# LM_HTR_001.net
KiCad netlist of a schematic drawn in Altium Designer
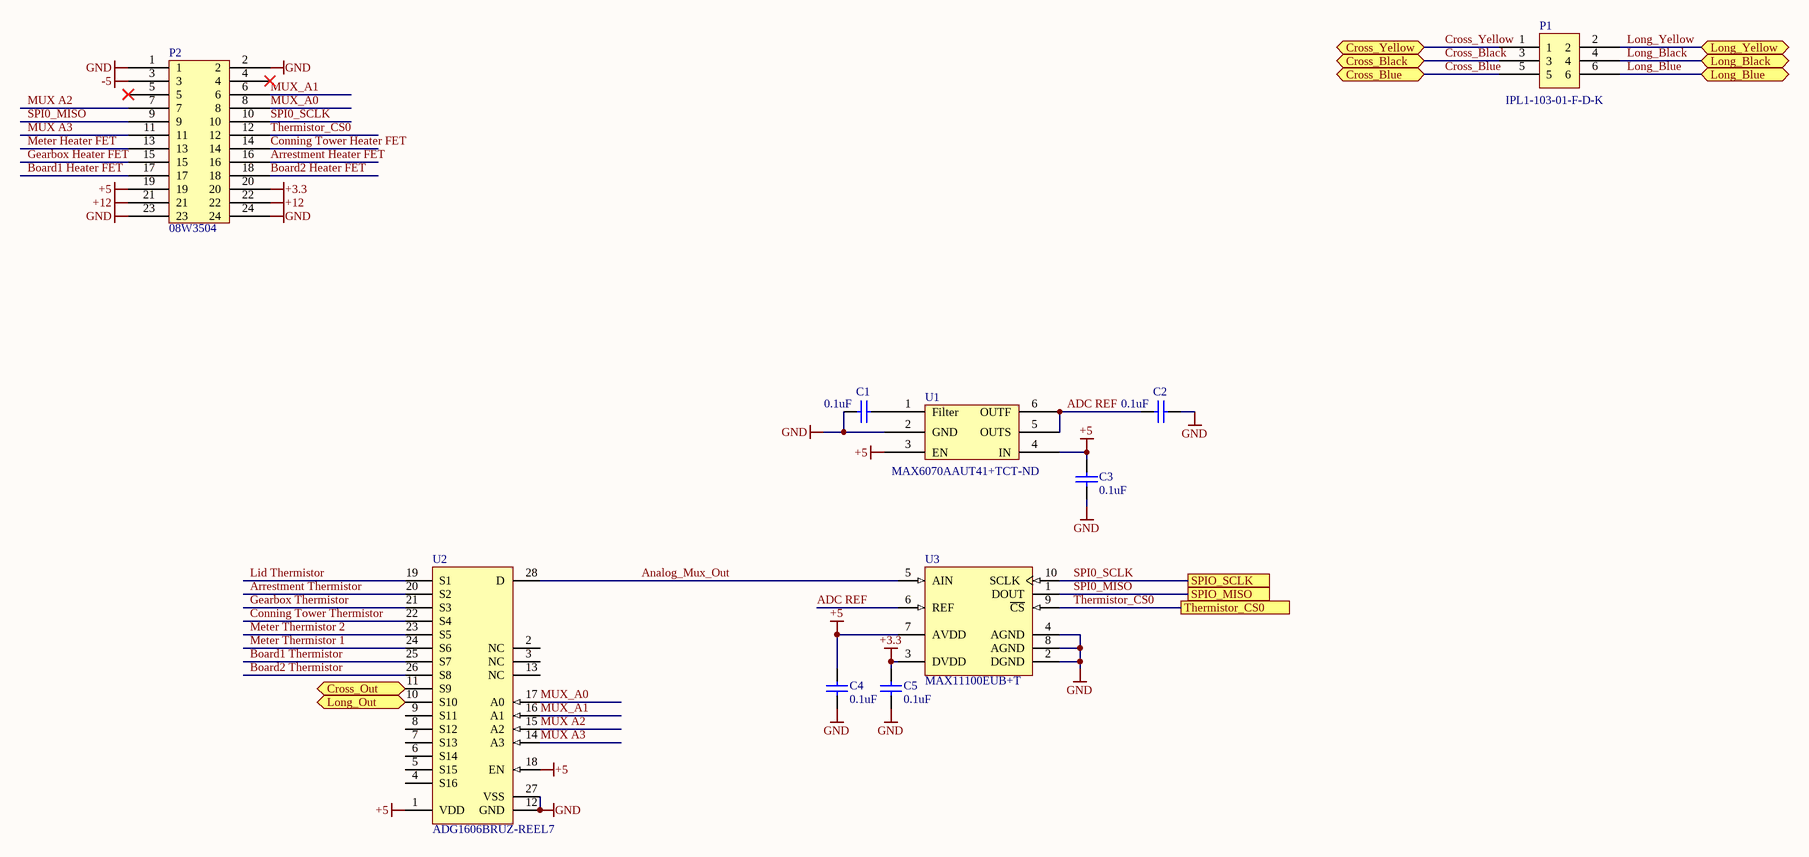
[diagram p0: LM_HTR_001.SchDoc]

(export (version "E")
  (design (tool "Eeschema 10.0.6"))
  (components
    (comp (ref "C1")
      (value "0.1uF")
      (footprint "CAPC0402(1005)60_L")
      (description "CAP CER 0.1UF 10V X7R 0402")
      (fields
        (field (name "MANUFACTURER") "Murata Electronics North America")
        (field (name "MANUFACTURER PART NUMBER") "GRM155R71A104KA01D")
      )
      (libsource (lib "Altium Content Vault") (part "CMP-1034-00252-1"))
    )
    (comp (ref "C2")
      (value "0.1uF")
      (footprint "CAPC0402(1005)60_L")
      (description "CAP CER 0.1UF 10V X7R 0402")
      (fields
        (field (name "MANUFACTURER") "Murata Electronics North America")
        (field (name "MANUFACTURER PART NUMBER") "GRM155R71A104KA01D")
      )
      (libsource (lib "Altium Content Vault") (part "CMP-1034-00252-1"))
    )
    (comp (ref "C3")
      (value "0.1uF")
      (footprint "CAPC0402(1005)60_L")
      (description "CAP CER 0.1UF 10V X7R 0402")
      (fields
        (field (name "MANUFACTURER") "Murata Electronics North America")
        (field (name "MANUFACTURER PART NUMBER") "GRM155R71A104KA01D")
      )
      (libsource (lib "Altium Content Vault") (part "CMP-1034-00252-1"))
    )
    (comp (ref "C4")
      (value "0.1uF")
      (footprint "CAPC0402(1005)60_L")
      (description "CAP CER 0.1UF 10V X7R 0402")
      (fields
        (field (name "MANUFACTURER") "Murata Electronics North America")
        (field (name "MANUFACTURER PART NUMBER") "GRM155R71A104KA01D")
      )
      (libsource (lib "Altium Content Vault") (part "CMP-1034-00252-1"))
    )
    (comp (ref "C5")
      (value "0.1uF")
      (footprint "CAPC0402(1005)60_L")
      (description "CAP CER 0.1UF 10V X7R 0402")
      (fields
        (field (name "MANUFACTURER") "Murata Electronics North America")
        (field (name "MANUFACTURER PART NUMBER") "GRM155R71A104KA01D")
      )
      (libsource (lib "Altium Content Vault") (part "CMP-1034-00252-1"))
    )
    (comp (ref "P1")
      (value "IPL1-103-01-F-D")
      (footprint "IPL1-103-01-F-D")
      (fields
        (field (name "MANUFACTURER") "SAMTEC")
        (field (name "MANUFACTURER PART NUMBER") "IPL1-103-01-F-D-K")
        (field (name "COMPONENTLINK1URL") "https://webassistants.partcommunity.com/23d-libs/samtec/search/resolve.html?EMAIL=mysamtec@samtec.com&PN=HTSW-114-05-F-D")
        (field (name "COMPONENTLINK1DESCRIPTION") "https://webassistants.partcommunity.com/23d-libs/samtec/search/resolve.html?EMAIL=mysamtec@samtec.com&PN=HTSW-114-05-F-D")
      )
      (libsource (lib "ZLS_Schematic_lib") (part "IPL1-103-01-F-D"))
    )
    (comp (ref "P2")
      (value "IPL1-112-01-F-S-K")
      (footprint "IPL1-112-01-F-S-K")
      (description "IPL1-112-01-F-D-K")
      (fields (field (name "SUPPLIER PART NUMBER 1") "08W3504"))
      (libsource (lib "ZLS_Schematic_lib") (part "IPL1-112-01-F-S-K"))
    )
    (comp (ref "U1")
      (value "MAX6070AAUT41+T")
      (footprint "SOT95P280X445-6N")
      (description "IC VREF SERIES 4.096V SOT23")
      (fields
        (field (name "SUPPLIER PART NUMBER 1") "MAX6070AAUT41+TCT-ND")
        (field (name "MANUFACTURER") "Maxim Integrated")
        (field (name "TOLERANCE") "±0.04%")
      )
      (libsource (lib "ZLS_Schematic_lib") (part "MAX6070AAUT41+T"))
    )
    (comp (ref "U2")
      (value "ADG1606BRUZ-REEL7")
      (footprint "ADI-RU-28_M")
      (description "4.5 Ohm Ron, 16-Channel, +/-5 V,+12 V,+5 V and +3.3 V Multiplexer, 28-pin SOP (RU-28), Reel")
      (fields (field (name "MANUFACTURER") "Analog Devices"))
      (libsource (lib "Altium Content Vault") (part "ADI-ADG1606-RU-28"))
    )
    (comp (ref "U3")
      (value "MAX11100EUB+T")
      (footprint "U10+2_L")
      (description "16-Bit, +5V, 200ksps ADC with 10uA Shutdown, 10-Pin uMAX, -40°C to +85°C, Pb-Free, Tape and Reel")
      (libsource (lib "Altium Content Vault") (part "CON-ADC-MAX11100-IL10"))
    )
  )
  (nets
    (net (code "1") (name "+3.3") (class "Default")
      (node (ref "C5") (pin "1") (pinfunction "1_1") (pintype "passive"))
      (node (ref "P2") (pin "20") (pinfunction "20_20") (pintype "passive"))
      (node (ref "U3") (pin "3") (pinfunction "DVDD_3") (pintype "power_in"))
    )
    (net (code "2") (name "+5") (class "Default")
      (node (ref "C3") (pin "1") (pinfunction "1_1") (pintype "passive"))
      (node (ref "C4") (pin "1") (pinfunction "1_1") (pintype "passive"))
      (node (ref "P2") (pin "19") (pinfunction "19_19") (pintype "passive"))
      (node (ref "U1") (pin "3") (pinfunction "EN_3") (pintype "passive"))
      (node (ref "U1") (pin "4") (pinfunction "IN_4") (pintype "passive"))
      (node (ref "U2") (pin "1") (pinfunction "VDD_1") (pintype "power_in"))
      (node (ref "U2") (pin "18") (pinfunction "EN_18") (pintype "input"))
      (node (ref "U3") (pin "7") (pinfunction "AVDD_7") (pintype "power_in"))
    )
    (net (code "3") (name "+12") (class "Default")
      (node (ref "P2") (pin "21") (pinfunction "21_21") (pintype "passive"))
      (node (ref "P2") (pin "22") (pinfunction "22_22") (pintype "passive"))
    )
    (net (code "4") (name "-5") (class "Default")
      (node (ref "P2") (pin "3") (pinfunction "3_3") (pintype "passive"))
    )
    (net (code "5") (name "/ADC REF") (class "Default")
      (node (ref "C2") (pin "2") (pinfunction "2_2") (pintype "passive"))
      (node (ref "U1") (pin "5") (pinfunction "OUTS_5") (pintype "passive"))
      (node (ref "U1") (pin "6") (pinfunction "OUTF_6") (pintype "passive"))
      (node (ref "U3") (pin "6") (pinfunction "REF_6") (pintype "input"))
    )
    (net (code "6") (name "/Analog_Mux_Out") (class "Default")
      (node (ref "U2") (pin "28") (pinfunction "D_28") (pintype "passive"))
      (node (ref "U3") (pin "5") (pinfunction "AIN_5") (pintype "input"))
    )
    (net (code "7") (name "/Arrestment Heater FET") (class "Default")
      (node (ref "P2") (pin "16") (pinfunction "16_16") (pintype "passive"))
    )
    (net (code "8") (name "/Arrestment Thermistor") (class "Default")
      (node (ref "U2") (pin "20") (pinfunction "S2_20") (pintype "passive"))
    )
    (net (code "9") (name "/Board1 Heater FET") (class "Default")
      (node (ref "P2") (pin "17") (pinfunction "17_17") (pintype "passive"))
    )
    (net (code "10") (name "/Board1 Thermistor") (class "Default")
      (node (ref "U2") (pin "25") (pinfunction "S7_25") (pintype "passive"))
    )
    (net (code "11") (name "/Board2 Heater FET") (class "Default")
      (node (ref "P2") (pin "18") (pinfunction "18_18") (pintype "passive"))
    )
    (net (code "12") (name "/Board2 Thermistor") (class "Default")
      (node (ref "U2") (pin "26") (pinfunction "S8_26") (pintype "passive"))
    )
    (net (code "13") (name "/Conning Tower Heater FET") (class "Default")
      (node (ref "P2") (pin "14") (pinfunction "14_14") (pintype "passive"))
    )
    (net (code "14") (name "/Conning Tower Thermistor") (class "Default")
      (node (ref "U2") (pin "22") (pinfunction "S4_22") (pintype "passive"))
    )
    (net (code "15") (name "/Cross_Black") (class "Default")
      (node (ref "P1") (pin "3") (pinfunction "3_3") (pintype "passive"))
    )
    (net (code "16") (name "/Cross_Blue") (class "Default")
      (node (ref "P1") (pin "5") (pinfunction "5_5") (pintype "passive"))
    )
    (net (code "17") (name "/Cross_Out") (class "Default")
      (node (ref "U2") (pin "11") (pinfunction "S9_11") (pintype "passive"))
    )
    (net (code "18") (name "/Cross_Yellow") (class "Default")
      (node (ref "P1") (pin "1") (pinfunction "1_1") (pintype "passive"))
    )
    (net (code "19") (name "/Gearbox Heater FET") (class "Default")
      (node (ref "P2") (pin "15") (pinfunction "15_15") (pintype "passive"))
    )
    (net (code "20") (name "/Gearbox Thermistor") (class "Default")
      (node (ref "U2") (pin "21") (pinfunction "S3_21") (pintype "passive"))
    )
    (net (code "21") (name "/Lid Thermistor") (class "Default")
      (node (ref "U2") (pin "19") (pinfunction "S1_19") (pintype "passive"))
    )
    (net (code "22") (name "/Long_Black") (class "Default")
      (node (ref "P1") (pin "4") (pinfunction "4_4") (pintype "passive"))
    )
    (net (code "23") (name "/Long_Blue") (class "Default")
      (node (ref "P1") (pin "6") (pinfunction "6_6") (pintype "passive"))
    )
    (net (code "24") (name "/Long_Out") (class "Default")
      (node (ref "U2") (pin "10") (pinfunction "S10_10") (pintype "passive"))
    )
    (net (code "25") (name "/Long_Yellow") (class "Default")
      (node (ref "P1") (pin "2") (pinfunction "2_2") (pintype "passive"))
    )
    (net (code "26") (name "/MUX A2") (class "Default")
      (node (ref "P2") (pin "7") (pinfunction "7_7") (pintype "passive"))
      (node (ref "U2") (pin "15") (pinfunction "A2_15") (pintype "input"))
    )
    (net (code "27") (name "/MUX A3") (class "Default")
      (node (ref "P2") (pin "11") (pinfunction "11_11") (pintype "passive"))
      (node (ref "U2") (pin "14") (pinfunction "A3_14") (pintype "input"))
    )
    (net (code "28") (name "/MUX_A0") (class "Default")
      (node (ref "P2") (pin "8") (pinfunction "8_8") (pintype "passive"))
      (node (ref "U2") (pin "17") (pinfunction "A0_17") (pintype "input"))
    )
    (net (code "29") (name "/MUX_A1") (class "Default")
      (node (ref "P2") (pin "6") (pinfunction "6_6") (pintype "passive"))
      (node (ref "U2") (pin "16") (pinfunction "A1_16") (pintype "input"))
    )
    (net (code "30") (name "/Meter Heater FET") (class "Default")
      (node (ref "P2") (pin "13") (pinfunction "13_13") (pintype "passive"))
    )
    (net (code "31") (name "/Meter Thermistor 1") (class "Default")
      (node (ref "U2") (pin "24") (pinfunction "S6_24") (pintype "passive"))
    )
    (net (code "32") (name "/Meter Thermistor 2") (class "Default")
      (node (ref "U2") (pin "23") (pinfunction "S5_23") (pintype "passive"))
    )
    (net (code "33") (name "/SPI0_MISO") (class "Default")
      (node (ref "P2") (pin "9") (pinfunction "9_9") (pintype "passive"))
      (node (ref "U3") (pin "1") (pinfunction "DOUT_1") (pintype "tri_state"))
    )
    (net (code "34") (name "/SPI0_SCLK") (class "Default")
      (node (ref "P2") (pin "10") (pinfunction "10_10") (pintype "passive"))
      (node (ref "U3") (pin "10") (pinfunction "SCLK_10") (pintype "input"))
    )
    (net (code "35") (name "/Thermistor_CS0") (class "Default")
      (node (ref "P2") (pin "12") (pinfunction "12_12") (pintype "passive"))
      (node (ref "U3") (pin "9") (pinfunction "~{CS}_9") (pintype "input"))
    )
    (net (code "36") (name "GND") (class "Default")
      (node (ref "C1") (pin "2") (pinfunction "2_2") (pintype "passive"))
      (node (ref "C2") (pin "1") (pinfunction "1_1") (pintype "passive"))
      (node (ref "C3") (pin "2") (pinfunction "2_2") (pintype "passive"))
      (node (ref "C4") (pin "2") (pinfunction "2_2") (pintype "passive"))
      (node (ref "C5") (pin "2") (pinfunction "2_2") (pintype "passive"))
      (node (ref "P2") (pin "1") (pinfunction "1_1") (pintype "passive"))
      (node (ref "P2") (pin "2") (pinfunction "2_2") (pintype "passive"))
      (node (ref "P2") (pin "23") (pinfunction "23_23") (pintype "passive"))
      (node (ref "P2") (pin "24") (pinfunction "24_24") (pintype "passive"))
      (node (ref "U1") (pin "2") (pinfunction "GND_2") (pintype "passive"))
      (node (ref "U2") (pin "12") (pinfunction "GND_12") (pintype "power_in"))
      (node (ref "U2") (pin "27") (pinfunction "VSS_27") (pintype "power_in"))
      (node (ref "U3") (pin "2") (pinfunction "DGND_2") (pintype "power_in"))
      (node (ref "U3") (pin "4") (pinfunction "AGND_4") (pintype "power_in"))
      (node (ref "U3") (pin "8") (pinfunction "AGND_8") (pintype "power_in"))
    )
    (net (code "37") (name "Net-(U1-Filter)") (class "Default")
      (node (ref "C1") (pin "1") (pinfunction "1_1") (pintype "passive"))
      (node (ref "U1") (pin "1") (pinfunction "Filter_1") (pintype "passive"))
    )
    (net (code "38") (name "unconnected-(P2-Pad4)") (class "Default")
      (node (ref "P2") (pin "4") (pinfunction "4_4") (pintype "passive+no_connect"))
    )
    (net (code "39") (name "unconnected-(P2-Pad5)") (class "Default")
      (node (ref "P2") (pin "5") (pinfunction "5_5") (pintype "passive+no_connect"))
    )
    (net (code "40") (name "unconnected-(U2-NC-Pad2)") (class "Default")
      (node (ref "U2") (pin "2") (pinfunction "NC_2") (pintype "passive"))
    )
    (net (code "41") (name "unconnected-(U2-NC-Pad3)") (class "Default")
      (node (ref "U2") (pin "3") (pinfunction "NC_3") (pintype "passive"))
    )
    (net (code "42") (name "unconnected-(U2-NC-Pad13)") (class "Default")
      (node (ref "U2") (pin "13") (pinfunction "NC_13") (pintype "passive"))
    )
    (net (code "43") (name "unconnected-(U2-S11-Pad9)") (class "Default")
      (node (ref "U2") (pin "9") (pinfunction "S11_9") (pintype "passive"))
    )
    (net (code "44") (name "unconnected-(U2-S12-Pad8)") (class "Default")
      (node (ref "U2") (pin "8") (pinfunction "S12_8") (pintype "passive"))
    )
    (net (code "45") (name "unconnected-(U2-S13-Pad7)") (class "Default")
      (node (ref "U2") (pin "7") (pinfunction "S13_7") (pintype "passive"))
    )
    (net (code "46") (name "unconnected-(U2-S14-Pad6)") (class "Default")
      (node (ref "U2") (pin "6") (pinfunction "S14_6") (pintype "passive"))
    )
    (net (code "47") (name "unconnected-(U2-S15-Pad5)") (class "Default")
      (node (ref "U2") (pin "5") (pinfunction "S15_5") (pintype "passive"))
    )
    (net (code "48") (name "unconnected-(U2-S16-Pad4)") (class "Default")
      (node (ref "U2") (pin "4") (pinfunction "S16_4") (pintype "passive"))
    )
  )
)
